# MilliNut.net
KiCad netlist of a schematic drawn in Altium Designer
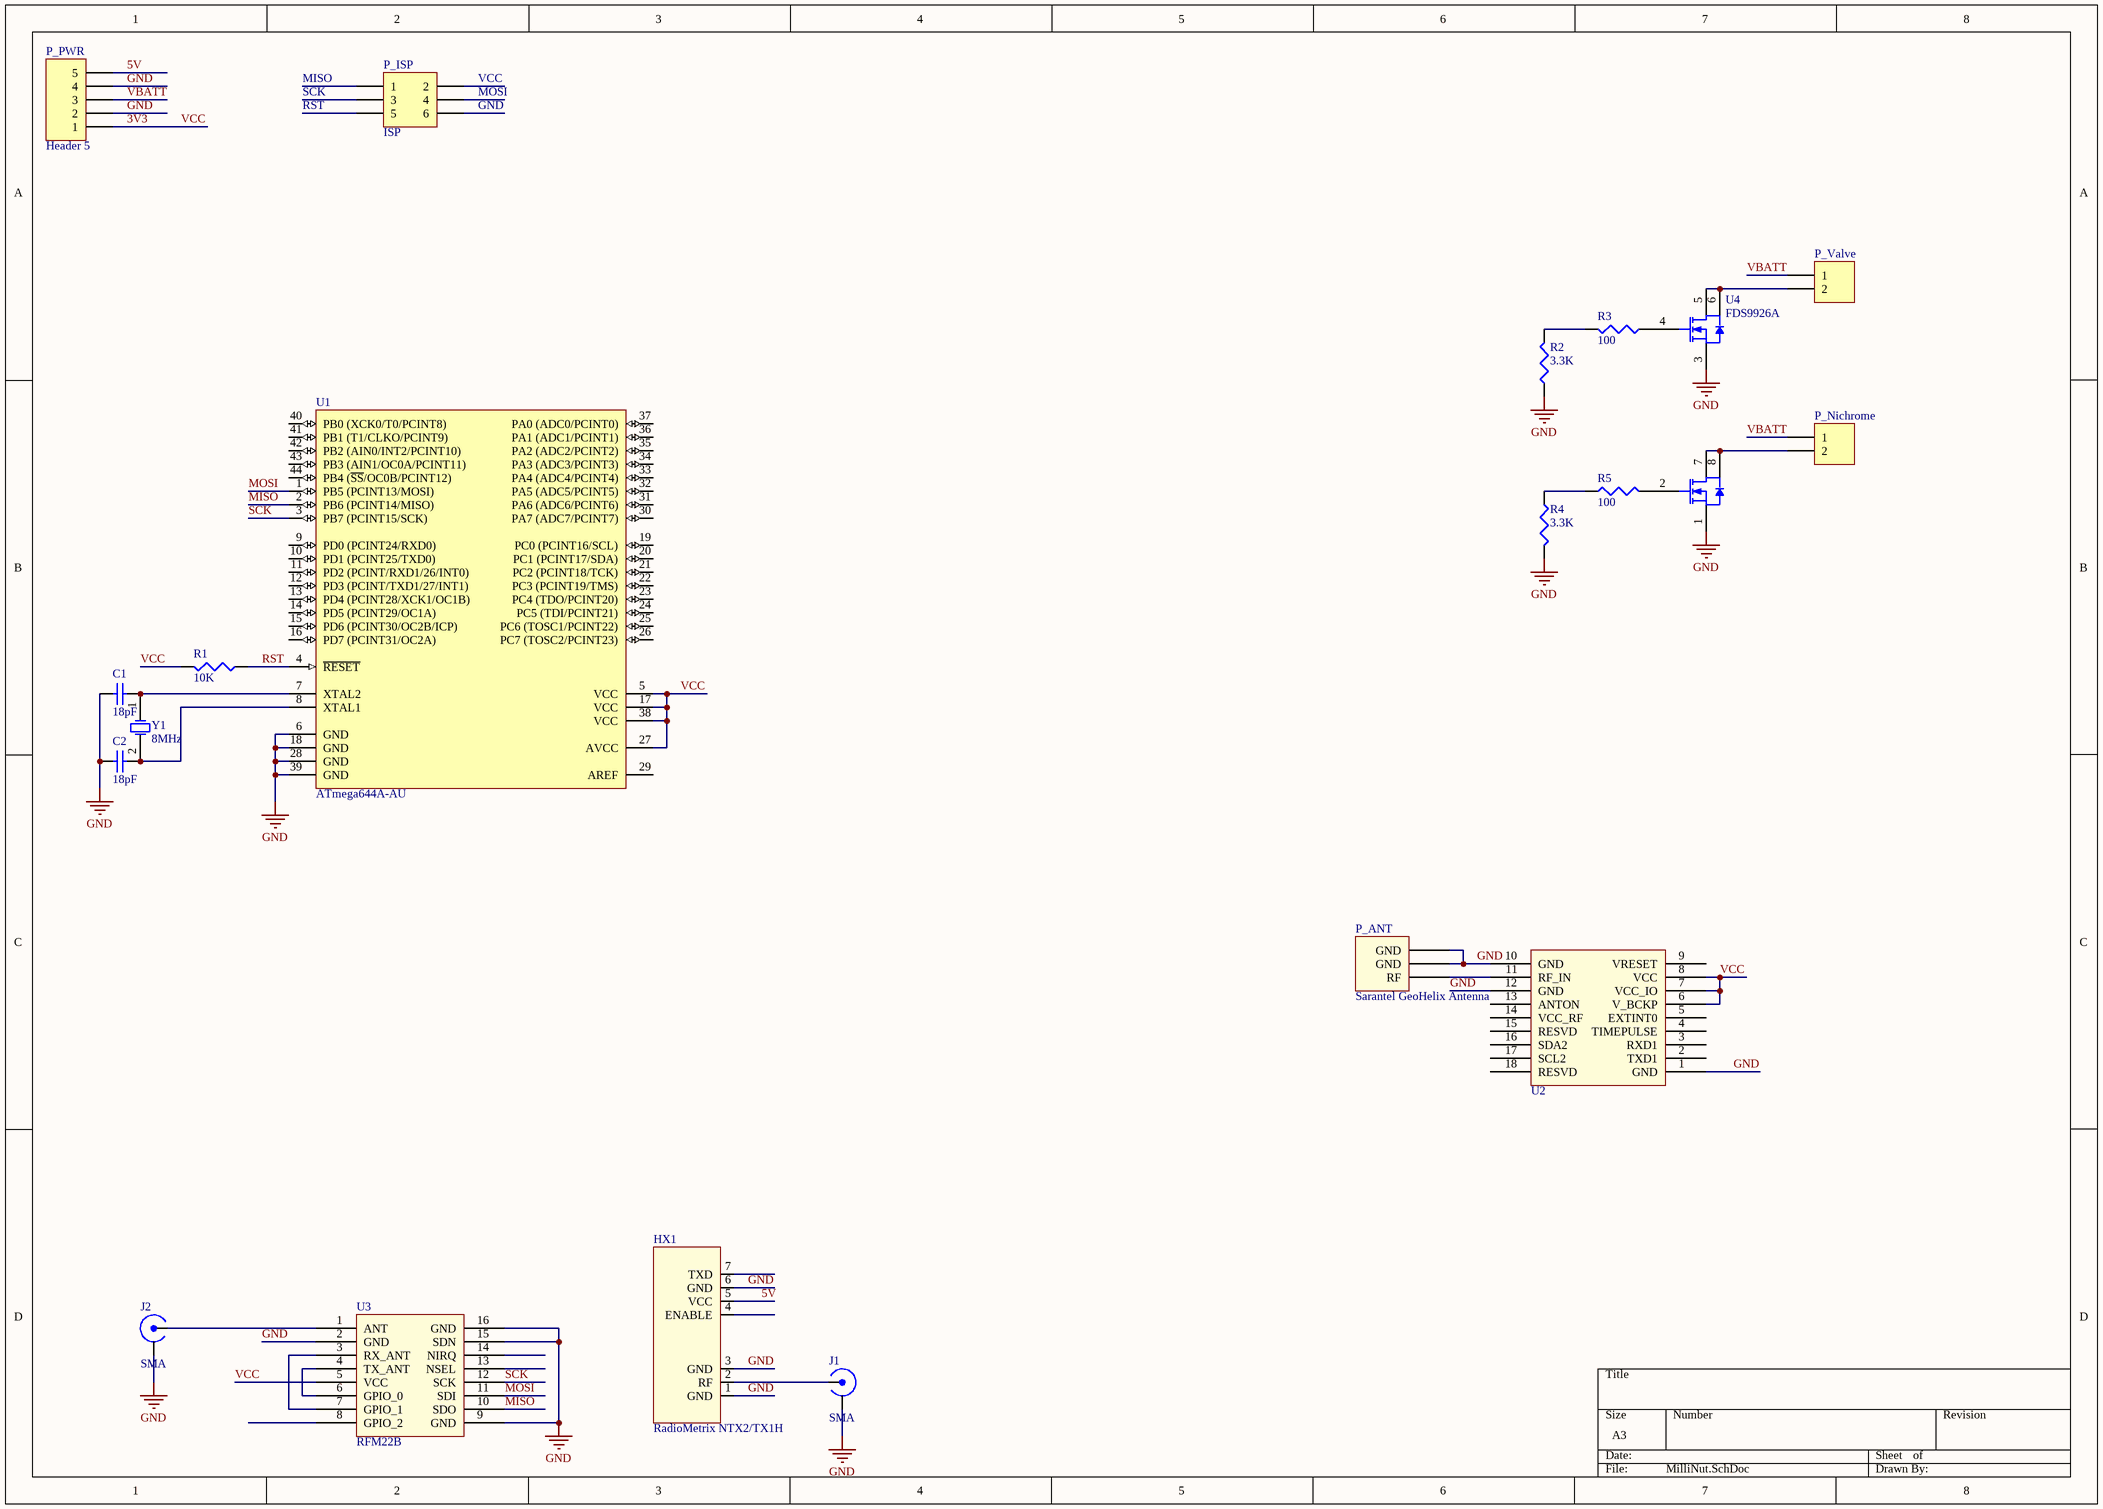
[diagram p0: MilliNut.SchDoc]

(export (version "E")
  (design (tool "Eeschema 10.0.6"))
  (components
    (comp (ref "C1")
      (value "18pF")
      (footprint "1608[0603]")
      (description "Ceramic Chip Capacitor - Standard")
      (fields (field (name "Comment") "C0805") (field (name "PUBLISHER") "Altium Limited"))
      (libsource (lib "KEMET Chip Capacitor") (part "C0805"))
    )
    (comp (ref "C2")
      (value "18pF")
      (footprint "1608[0603]")
      (description "Ceramic Chip Capacitor - Standard")
      (fields (field (name "Comment") "C0805") (field (name "PUBLISHER") "Altium Limited"))
      (libsource (lib "KEMET Chip Capacitor") (part "C0805"))
    )
    (comp (ref "HX1")
      (value "RadioMetrix NTX2/TX1H")
      (footprint "HX1_Vertical")
      (libsource (lib "Darkside_Lib") (part "RadioMetrix NTX2/TX1H"))
    )
    (comp (ref "J1")
      (value "SMA")
      (footprint "Darkside_Lib:CON SMA PCB 90")
      (description "Power Connector")
      (fields (field (name "Comment") "SMA_L"))
      (libsource (lib "") (part "SMA_L_1"))
    )
    (comp (ref "J2")
      (value "SMA")
      (footprint "Darkside_Lib:CON SMA PCB 90")
      (description "Power Connector")
      (fields (field (name "Comment") "SMA_L"))
      (libsource (lib "Darkside_Lib") (part "SMA_L"))
    )
    (comp (ref "P_ANT")
      (value "Sarantel GeoHelix Antenna")
      (footprint "Darkside_Lib:Sarantel SL1202RH")
      (libsource (lib "Darkside_Lib") (part "Sarantel GeoHelix Antenna"))
    )
    (comp (ref "P_ISP")
      (value "ISP")
      (footprint "HDR2X3")
      (description "Header, 3-Pin, Dual row")
      (fields (field (name "PUBLISHER") "Altium Limited"))
      (libsource (lib "Miscellaneous Connectors") (part "Header 3X2"))
    )
    (comp (ref "P_Nichrome")
      (value "Header 2")
      (footprint "HDR1X2")
      (description "Header, 2-Pin")
      (fields (field (name "PUBLISHER") "Altium Limited"))
      (libsource (lib "Miscellaneous Connectors") (part "Header 2"))
    )
    (comp (ref "P_PWR")
      (value "Header 5")
      (footprint "HDR1X5")
      (description "Header, 5-Pin")
      (fields (field (name "PUBLISHER") "Altium Limited"))
      (libsource (lib "Miscellaneous Connectors") (part "Header 5"))
    )
    (comp (ref "P_Valve")
      (value "Header 2")
      (footprint "HDR1X2")
      (description "Header, 2-Pin")
      (fields (field (name "PUBLISHER") "Altium Limited"))
      (libsource (lib "Miscellaneous Connectors") (part "Header 2"))
    )
    (comp (ref "R1")
      (value "10K")
      (footprint "J1-0603")
      (description "Resistor")
      (fields (field (name "Comment") "Res3") (field (name "PUBLISHER") "Altium Limited"))
      (libsource (lib "Miscellaneous Devices") (part "Res3"))
    )
    (comp (ref "R2")
      (value "3.3K")
      (description "Resistor")
      (fields (field (name "Comment") "Res3") (field (name "PUBLISHER") "Altium Limited"))
      (libsource (lib "Miscellaneous Devices") (part "Res3"))
    )
    (comp (ref "R3")
      (value "100")
      (description "Resistor")
      (fields (field (name "Comment") "Res3") (field (name "PUBLISHER") "Altium Limited"))
      (libsource (lib "Miscellaneous Devices") (part "Res3"))
    )
    (comp (ref "R4")
      (value "3.3K")
      (description "Resistor")
      (fields (field (name "Comment") "Res3") (field (name "PUBLISHER") "Altium Limited"))
      (libsource (lib "Miscellaneous Devices") (part "Res3"))
    )
    (comp (ref "R5")
      (value "100")
      (description "Resistor")
      (fields (field (name "Comment") "Res3") (field (name "PUBLISHER") "Altium Limited"))
      (libsource (lib "Miscellaneous Devices") (part "Res3"))
    )
    (comp (ref "U1")
      (value "ATmega644A-AU")
      (footprint "44A_M")
      (fields (field (name "PUBLISHER") "Altium Limited"))
      (libsource (lib "Atmel Microcontroller 8-Bit megaAVR") (part "ATmega644A-AU"))
    )
    (comp (ref "U2")
      (value "uBlox MAX-6Q")
      (footprint "MAX-6Q")
      (libsource (lib "Darkside_Lib") (part "uBlox MAX-6Q"))
    )
    (comp (ref "U3")
      (value "RFM22B")
      (footprint "RFM22B")
      (libsource (lib "Darkside_Lib") (part "RFM22B-S2"))
    )
    (comp (ref "U4")
      (value "FDS9926A")
      (footprint "SO8_M")
      (libsource (lib "Darkside_Lib") (part "FDS9926A"))
    )
    (comp (ref "Y1")
      (value "8MHz")
      (footprint "ABM3_XTAL")
      (description "Crystal Oscillator")
      (fields (field (name "PUBLISHER") "Altium Limited"))
      (libsource (lib "ECS Crystal Oscillator") (part "ECS-110-S-1"))
    )
  )
  (nets
    (net (code "1") (name "/3V3") (class "Default")
      (node (ref "P_ISP") (pin "2") (pinfunction "2_2") (pintype "passive"))
      (node (ref "P_PWR") (pin "1") (pinfunction "1_1") (pintype "passive"))
      (node (ref "R1") (pin "2") (pinfunction "2_2") (pintype "passive"))
      (node (ref "U1") (pin "17") (pinfunction "VCC_17") (pintype "power_in"))
      (node (ref "U1") (pin "27") (pinfunction "AVCC_27") (pintype "power_in"))
      (node (ref "U1") (pin "38") (pinfunction "VCC_38") (pintype "power_in"))
      (node (ref "U1") (pin "5") (pinfunction "VCC_5") (pintype "power_in"))
      (node (ref "U2") (pin "6") (pinfunction "V_BCKP_6") (pintype "passive"))
      (node (ref "U2") (pin "7") (pinfunction "VCC_IO_7") (pintype "passive"))
      (node (ref "U2") (pin "8") (pinfunction "VCC_8") (pintype "passive"))
      (node (ref "U3") (pin "5") (pinfunction "VCC_5") (pintype "passive"))
    )
    (net (code "2") (name "/5V") (class "Default")
      (node (ref "HX1") (pin "5") (pinfunction "VCC_5") (pintype "passive"))
      (node (ref "P_PWR") (pin "5") (pinfunction "5_5") (pintype "passive"))
    )
    (net (code "3") (name "/MISO") (class "Default")
      (node (ref "P_ISP") (pin "1") (pinfunction "1_1") (pintype "passive"))
      (node (ref "U1") (pin "2") (pinfunction "PB6_(PCINT14/MISO)_2") (pintype "bidirectional"))
      (node (ref "U3") (pin "10") (pinfunction "SDO_10") (pintype "passive"))
    )
    (net (code "4") (name "/MOSI") (class "Default")
      (node (ref "P_ISP") (pin "4") (pinfunction "4_4") (pintype "passive"))
      (node (ref "U1") (pin "1") (pinfunction "PB5_(PCINT13/MOSI)_1") (pintype "bidirectional"))
      (node (ref "U3") (pin "11") (pinfunction "SDI_11") (pintype "passive"))
    )
    (net (code "5") (name "/RST") (class "Default")
      (node (ref "P_ISP") (pin "5") (pinfunction "5_5") (pintype "passive"))
      (node (ref "R1") (pin "1") (pinfunction "1_1") (pintype "passive"))
      (node (ref "U1") (pin "4") (pinfunction "~{RESET}_4") (pintype "input"))
    )
    (net (code "6") (name "/SCK") (class "Default")
      (node (ref "P_ISP") (pin "3") (pinfunction "3_3") (pintype "passive"))
      (node (ref "U1") (pin "3") (pinfunction "PB7_(PCINT15/SCK)_3") (pintype "bidirectional"))
      (node (ref "U3") (pin "12") (pinfunction "SCK_12") (pintype "passive"))
    )
    (net (code "7") (name "/VBATT") (class "Default")
      (node (ref "P_Nichrome") (pin "1") (pinfunction "1_1") (pintype "passive"))
      (node (ref "P_PWR") (pin "3") (pinfunction "3_3") (pintype "passive"))
      (node (ref "P_Valve") (pin "1") (pinfunction "1_1") (pintype "passive"))
    )
    (net (code "8") (name "GND") (class "Default")
      (node (ref "C1") (pin "1") (pinfunction "1_1") (pintype "passive"))
      (node (ref "C2") (pin "1") (pinfunction "1_1") (pintype "passive"))
      (node (ref "HX1") (pin "1") (pinfunction "GND_1") (pintype "passive"))
      (node (ref "HX1") (pin "3") (pinfunction "GND_3") (pintype "passive"))
      (node (ref "HX1") (pin "6") (pinfunction "GND_6") (pintype "passive"))
      (node (ref "J1") (pin "2") (pinfunction "2_2") (pintype "passive"))
      (node (ref "J2") (pin "2") (pinfunction "2_2") (pintype "passive"))
      (node (ref "P_ANT") (pin "2") (pinfunction "GND_2") (pintype "passive"))
      (node (ref "P_ANT") (pin "3") (pinfunction "GND_3") (pintype "passive"))
      (node (ref "P_ISP") (pin "6") (pinfunction "6_6") (pintype "passive"))
      (node (ref "P_PWR") (pin "2") (pinfunction "2_2") (pintype "passive"))
      (node (ref "P_PWR") (pin "4") (pinfunction "4_4") (pintype "passive"))
      (node (ref "R2") (pin "1") (pinfunction "1_1") (pintype "passive"))
      (node (ref "R4") (pin "2") (pinfunction "2_2") (pintype "passive"))
      (node (ref "U1") (pin "18") (pinfunction "GND_18") (pintype "power_in"))
      (node (ref "U1") (pin "28") (pinfunction "GND_28") (pintype "power_in"))
      (node (ref "U1") (pin "39") (pinfunction "GND_39") (pintype "power_in"))
      (node (ref "U1") (pin "6") (pinfunction "GND_6") (pintype "power_in"))
      (node (ref "U2") (pin "1") (pinfunction "GND_1") (pintype "passive"))
      (node (ref "U2") (pin "10") (pinfunction "GND_10") (pintype "passive"))
      (node (ref "U2") (pin "12") (pinfunction "GND_12") (pintype "passive"))
      (node (ref "U3") (pin "15") (pinfunction "SDN_15") (pintype "passive"))
      (node (ref "U3") (pin "16") (pinfunction "GND_16") (pintype "passive"))
      (node (ref "U3") (pin "2") (pinfunction "GND_2") (pintype "passive"))
      (node (ref "U3") (pin "9") (pinfunction "GND_9") (pintype "passive"))
      (node (ref "U4") (pin "1") (pinfunction "S_1") (pintype "passive"))
      (node (ref "U4") (pin "3") (pinfunction "S_3") (pintype "passive"))
    )
    (net (code "9") (name "Net-(HX1-RF)") (class "Default")
      (node (ref "HX1") (pin "2") (pinfunction "RF_2") (pintype "passive"))
      (node (ref "J1") (pin "1") (pinfunction "1_1") (pintype "passive"))
    )
    (net (code "10") (name "Net-(P_ANT-RF)") (class "Default")
      (node (ref "P_ANT") (pin "1") (pinfunction "RF_1") (pintype "passive"))
      (node (ref "U2") (pin "11") (pinfunction "RF_IN_11") (pintype "passive"))
    )
    (net (code "11") (name "Net-(P_Nichrome-Pad2)") (class "Default")
      (node (ref "P_Nichrome") (pin "2") (pinfunction "2_2") (pintype "passive"))
      (node (ref "U4") (pin "7") (pinfunction "D_7") (pintype "passive"))
      (node (ref "U4") (pin "8") (pinfunction "D_8") (pintype "passive"))
    )
    (net (code "12") (name "Net-(P_Valve-Pad2)") (class "Default")
      (node (ref "P_Valve") (pin "2") (pinfunction "2_2") (pintype "passive"))
      (node (ref "U4") (pin "5") (pinfunction "D_5") (pintype "passive"))
      (node (ref "U4") (pin "6") (pinfunction "D_6") (pintype "passive"))
    )
    (net (code "13") (name "Net-(R2-Pad2)") (class "Default")
      (node (ref "R2") (pin "2") (pinfunction "2_2") (pintype "passive"))
      (node (ref "R3") (pin "2") (pinfunction "2_2") (pintype "passive"))
    )
    (net (code "14") (name "Net-(R3-Pad1)") (class "Default")
      (node (ref "R3") (pin "1") (pinfunction "1_1") (pintype "passive"))
      (node (ref "U4") (pin "4") (pinfunction "G_4") (pintype "passive"))
    )
    (net (code "15") (name "Net-(R4-Pad1)") (class "Default")
      (node (ref "R4") (pin "1") (pinfunction "1_1") (pintype "passive"))
      (node (ref "R5") (pin "1") (pinfunction "1_1") (pintype "passive"))
    )
    (net (code "16") (name "Net-(R5-Pad2)") (class "Default")
      (node (ref "R5") (pin "2") (pinfunction "2_2") (pintype "passive"))
      (node (ref "U4") (pin "2") (pinfunction "G_2") (pintype "passive"))
    )
    (net (code "17") (name "Net-(U1-XTAL1)") (class "Default")
      (node (ref "C2") (pin "2") (pinfunction "2_2") (pintype "passive"))
      (node (ref "U1") (pin "8") (pinfunction "XTAL1_8") (pintype "passive"))
      (node (ref "Y1") (pin "2") (pinfunction "OSC2_2") (pintype "passive"))
    )
    (net (code "18") (name "Net-(U1-XTAL2)") (class "Default")
      (node (ref "C1") (pin "2") (pinfunction "2_2") (pintype "passive"))
      (node (ref "U1") (pin "7") (pinfunction "XTAL2_7") (pintype "passive"))
      (node (ref "Y1") (pin "1") (pinfunction "OSC1_1") (pintype "passive"))
    )
    (net (code "19") (name "Net-(U3-ANT)") (class "Default")
      (node (ref "J2") (pin "1") (pinfunction "1_1") (pintype "passive"))
      (node (ref "U3") (pin "1") (pinfunction "ANT_1") (pintype "passive"))
    )
    (net (code "20") (name "Net-(U3-GPIO_0)") (class "Default")
      (node (ref "U3") (pin "4") (pinfunction "TX_ANT_4") (pintype "passive"))
      (node (ref "U3") (pin "6") (pinfunction "GPIO_0_6") (pintype "passive"))
    )
    (net (code "21") (name "Net-(U3-GPIO_1)") (class "Default")
      (node (ref "U3") (pin "3") (pinfunction "RX_ANT_3") (pintype "passive"))
      (node (ref "U3") (pin "7") (pinfunction "GPIO_1_7") (pintype "passive"))
    )
    (net (code "22") (name "unconnected-(HX1-ENABLE-Pad4)") (class "Default")
      (node (ref "HX1") (pin "4") (pinfunction "ENABLE_4") (pintype "passive"))
    )
    (net (code "23") (name "unconnected-(HX1-TXD-Pad7)") (class "Default")
      (node (ref "HX1") (pin "7") (pinfunction "TXD_7") (pintype "passive"))
    )
    (net (code "24") (name "unconnected-(U1-AREF-Pad29)") (class "Default")
      (node (ref "U1") (pin "29") (pinfunction "AREF_29") (pintype "power_in"))
    )
    (net (code "25") (name "unconnected-(U1-PA0_(ADC0{slash}PCINT0)-Pad37)") (class "Default")
      (node (ref "U1") (pin "37") (pinfunction "PA0_(ADC0/PCINT0)_37") (pintype "bidirectional"))
    )
    (net (code "26") (name "unconnected-(U1-PA1_(ADC1{slash}PCINT1)-Pad36)") (class "Default")
      (node (ref "U1") (pin "36") (pinfunction "PA1_(ADC1/PCINT1)_36") (pintype "bidirectional"))
    )
    (net (code "27") (name "unconnected-(U1-PA2_(ADC2{slash}PCINT2)-Pad35)") (class "Default")
      (node (ref "U1") (pin "35") (pinfunction "PA2_(ADC2/PCINT2)_35") (pintype "bidirectional"))
    )
    (net (code "28") (name "unconnected-(U1-PA3_(ADC3{slash}PCINT3)-Pad34)") (class "Default")
      (node (ref "U1") (pin "34") (pinfunction "PA3_(ADC3/PCINT3)_34") (pintype "bidirectional"))
    )
    (net (code "29") (name "unconnected-(U1-PA4_(ADC4{slash}PCINT4)-Pad33)") (class "Default")
      (node (ref "U1") (pin "33") (pinfunction "PA4_(ADC4/PCINT4)_33") (pintype "bidirectional"))
    )
    (net (code "30") (name "unconnected-(U1-PA5_(ADC5{slash}PCINT5)-Pad32)") (class "Default")
      (node (ref "U1") (pin "32") (pinfunction "PA5_(ADC5/PCINT5)_32") (pintype "bidirectional"))
    )
    (net (code "31") (name "unconnected-(U1-PA6_(ADC6{slash}PCINT6)-Pad31)") (class "Default")
      (node (ref "U1") (pin "31") (pinfunction "PA6_(ADC6/PCINT6)_31") (pintype "bidirectional"))
    )
    (net (code "32") (name "unconnected-(U1-PA7_(ADC7{slash}PCINT7)-Pad30)") (class "Default")
      (node (ref "U1") (pin "30") (pinfunction "PA7_(ADC7/PCINT7)_30") (pintype "bidirectional"))
    )
    (net (code "33") (name "unconnected-(U1-PB0_(XCK0{slash}T0{slash}PCINT8)-Pad40)") (class "Default")
      (node (ref "U1") (pin "40") (pinfunction "PB0_(XCK0/T0/PCINT8)_40") (pintype "bidirectional"))
    )
    (net (code "34") (name "unconnected-(U1-PB1_(T1{slash}CLKO{slash}PCINT9)-Pad41)") (class "Default")
      (node (ref "U1") (pin "41") (pinfunction "PB1_(T1/CLKO/PCINT9)_41") (pintype "bidirectional"))
    )
    (net (code "35") (name "unconnected-(U1-PB2_(AIN0{slash}INT2{slash}PCINT10)-Pad42)") (class "Default")
      (node (ref "U1") (pin "42") (pinfunction "PB2_(AIN0/INT2/PCINT10)_42") (pintype "bidirectional"))
    )
    (net (code "36") (name "unconnected-(U1-PB3_(AIN1{slash}OC0A{slash}PCINT11)-Pad43)") (class "Default")
      (node (ref "U1") (pin "43") (pinfunction "PB3_(AIN1/OC0A/PCINT11)_43") (pintype "bidirectional"))
    )
    (net (code "37") (name "unconnected-(U1-PB4_(~{SS}{slash}OC0B{slash}PCINT12)-Pad44)") (class "Default")
      (node (ref "U1") (pin "44") (pinfunction "PB4_(~{SS}/OC0B/PCINT12)_44") (pintype "bidirectional"))
    )
    (net (code "38") (name "unconnected-(U1-PC0_(PCINT16{slash}SCL)-Pad19)") (class "Default")
      (node (ref "U1") (pin "19") (pinfunction "PC0_(PCINT16/SCL)_19") (pintype "bidirectional"))
    )
    (net (code "39") (name "unconnected-(U1-PC1_(PCINT17{slash}SDA)-Pad20)") (class "Default")
      (node (ref "U1") (pin "20") (pinfunction "PC1_(PCINT17/SDA)_20") (pintype "bidirectional"))
    )
    (net (code "40") (name "unconnected-(U1-PC2_(PCINT18{slash}TCK)-Pad21)") (class "Default")
      (node (ref "U1") (pin "21") (pinfunction "PC2_(PCINT18/TCK)_21") (pintype "bidirectional"))
    )
    (net (code "41") (name "unconnected-(U1-PC3_(PCINT19{slash}TMS)-Pad22)") (class "Default")
      (node (ref "U1") (pin "22") (pinfunction "PC3_(PCINT19/TMS)_22") (pintype "bidirectional"))
    )
    (net (code "42") (name "unconnected-(U1-PC4_(TDO{slash}PCINT20)-Pad23)") (class "Default")
      (node (ref "U1") (pin "23") (pinfunction "PC4_(TDO/PCINT20)_23") (pintype "bidirectional"))
    )
    (net (code "43") (name "unconnected-(U1-PC5_(TDI{slash}PCINT21)-Pad24)") (class "Default")
      (node (ref "U1") (pin "24") (pinfunction "PC5_(TDI/PCINT21)_24") (pintype "bidirectional"))
    )
    (net (code "44") (name "unconnected-(U1-PC6_(TOSC1{slash}PCINT22)-Pad25)") (class "Default")
      (node (ref "U1") (pin "25") (pinfunction "PC6_(TOSC1/PCINT22)_25") (pintype "bidirectional"))
    )
    (net (code "45") (name "unconnected-(U1-PC7_(TOSC2{slash}PCINT23)-Pad26)") (class "Default")
      (node (ref "U1") (pin "26") (pinfunction "PC7_(TOSC2/PCINT23)_26") (pintype "bidirectional"))
    )
    (net (code "46") (name "unconnected-(U1-PD0_(PCINT24{slash}RXD0)-Pad9)") (class "Default")
      (node (ref "U1") (pin "9") (pinfunction "PD0_(PCINT24/RXD0)_9") (pintype "bidirectional"))
    )
    (net (code "47") (name "unconnected-(U1-PD1_(PCINT25{slash}TXD0)-Pad10)") (class "Default")
      (node (ref "U1") (pin "10") (pinfunction "PD1_(PCINT25/TXD0)_10") (pintype "bidirectional"))
    )
    (net (code "48") (name "unconnected-(U1-PD2_(PCINT{slash}RXD1{slash}26{slash}INT0)-Pad11)") (class "Default")
      (node (ref "U1") (pin "11") (pinfunction "PD2_(PCINT/RXD1/26/INT0)_11") (pintype "bidirectional"))
    )
    (net (code "49") (name "unconnected-(U1-PD3_(PCINT{slash}TXD1{slash}27{slash}INT1)-Pad12)") (class "Default")
      (node (ref "U1") (pin "12") (pinfunction "PD3_(PCINT/TXD1/27/INT1)_12") (pintype "bidirectional"))
    )
    (net (code "50") (name "unconnected-(U1-PD4_(PCINT28{slash}XCK1{slash}OC1B)-Pad13)") (class "Default")
      (node (ref "U1") (pin "13") (pinfunction "PD4_(PCINT28/XCK1/OC1B)_13") (pintype "bidirectional"))
    )
    (net (code "51") (name "unconnected-(U1-PD5_(PCINT29{slash}OC1A)-Pad14)") (class "Default")
      (node (ref "U1") (pin "14") (pinfunction "PD5_(PCINT29/OC1A)_14") (pintype "bidirectional"))
    )
    (net (code "52") (name "unconnected-(U1-PD6_(PCINT30{slash}OC2B{slash}ICP)-Pad15)") (class "Default")
      (node (ref "U1") (pin "15") (pinfunction "PD6_(PCINT30/OC2B/ICP)_15") (pintype "bidirectional"))
    )
    (net (code "53") (name "unconnected-(U1-PD7_(PCINT31{slash}OC2A)-Pad16)") (class "Default")
      (node (ref "U1") (pin "16") (pinfunction "PD7_(PCINT31/OC2A)_16") (pintype "bidirectional"))
    )
    (net (code "54") (name "unconnected-(U2-ANTON-Pad13)") (class "Default")
      (node (ref "U2") (pin "13") (pinfunction "ANTON_13") (pintype "passive"))
    )
    (net (code "55") (name "unconnected-(U2-EXTINT0-Pad5)") (class "Default")
      (node (ref "U2") (pin "5") (pinfunction "EXTINT0_5") (pintype "passive"))
    )
    (net (code "56") (name "unconnected-(U2-RESVD-Pad15)") (class "Default")
      (node (ref "U2") (pin "15") (pinfunction "RESVD_15") (pintype "passive"))
    )
    (net (code "57") (name "unconnected-(U2-RESVD-Pad18)") (class "Default")
      (node (ref "U2") (pin "18") (pinfunction "RESVD_18") (pintype "passive"))
    )
    (net (code "58") (name "unconnected-(U2-RXD1-Pad3)") (class "Default")
      (node (ref "U2") (pin "3") (pinfunction "RXD1_3") (pintype "passive"))
    )
    (net (code "59") (name "unconnected-(U2-SCL2-Pad17)") (class "Default")
      (node (ref "U2") (pin "17") (pinfunction "SCL2_17") (pintype "passive"))
    )
    (net (code "60") (name "unconnected-(U2-SDA2-Pad16)") (class "Default")
      (node (ref "U2") (pin "16") (pinfunction "SDA2_16") (pintype "passive"))
    )
    (net (code "61") (name "unconnected-(U2-TIMEPULSE-Pad4)") (class "Default")
      (node (ref "U2") (pin "4") (pinfunction "TIMEPULSE_4") (pintype "passive"))
    )
    (net (code "62") (name "unconnected-(U2-TXD1-Pad2)") (class "Default")
      (node (ref "U2") (pin "2") (pinfunction "TXD1_2") (pintype "passive"))
    )
    (net (code "63") (name "unconnected-(U2-VCC_RF-Pad14)") (class "Default")
      (node (ref "U2") (pin "14") (pinfunction "VCC_RF_14") (pintype "passive"))
    )
    (net (code "64") (name "unconnected-(U2-VRESET-Pad9)") (class "Default")
      (node (ref "U2") (pin "9") (pinfunction "VRESET_9") (pintype "passive"))
    )
    (net (code "65") (name "unconnected-(U3-GPIO_2-Pad8)") (class "Default")
      (node (ref "U3") (pin "8") (pinfunction "GPIO_2_8") (pintype "passive"))
    )
    (net (code "66") (name "unconnected-(U3-NIRQ-Pad14)") (class "Default")
      (node (ref "U3") (pin "14") (pinfunction "NIRQ_14") (pintype "passive"))
    )
    (net (code "67") (name "unconnected-(U3-NSEL-Pad13)") (class "Default")
      (node (ref "U3") (pin "13") (pinfunction "NSEL_13") (pintype "passive"))
    )
  )
)
